# pig_led.net
KiCad netlist of a schematic drawn in EAGLE
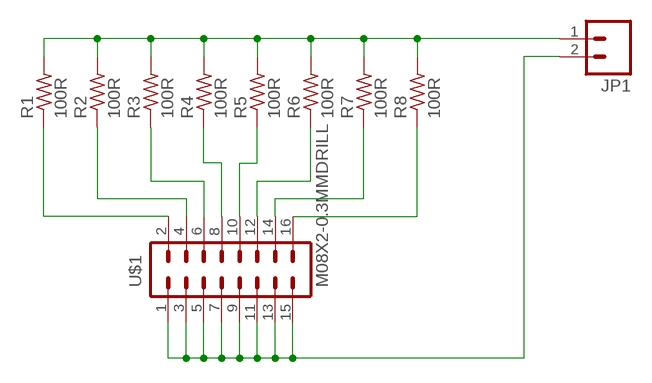
[diagram p0: schematic, sheet 1]

(export (version "E")
  (design (tool "Eeschema 10.0.6"))
  (components
    (comp (ref "JP1")
      (value "M023.5MM")
      (footprint "eagle-import:SCREWTERMINAL-3.5MM-2")
      (libsource (lib "eagle-import") (part "M023.5MM"))
    )
    (comp (ref "R1")
      (value "100R")
      (footprint "eagle-import:0207_10")
      (libsource (lib "eagle-import") (part "RESISTOR0207/10"))
    )
    (comp (ref "R2")
      (value "100R")
      (footprint "eagle-import:0207_10")
      (libsource (lib "eagle-import") (part "RESISTOR0207/10"))
    )
    (comp (ref "R3")
      (value "100R")
      (footprint "eagle-import:0207_10")
      (libsource (lib "eagle-import") (part "RESISTOR0207/10"))
    )
    (comp (ref "R4")
      (value "100R")
      (footprint "eagle-import:0207_10")
      (libsource (lib "eagle-import") (part "RESISTOR0207/10"))
    )
    (comp (ref "R5")
      (value "100R")
      (footprint "eagle-import:0207_10")
      (libsource (lib "eagle-import") (part "RESISTOR0207/10"))
    )
    (comp (ref "R6")
      (value "100R")
      (footprint "eagle-import:0207_10")
      (libsource (lib "eagle-import") (part "RESISTOR0207/10"))
    )
    (comp (ref "R7")
      (value "100R")
      (footprint "eagle-import:0207_10")
      (libsource (lib "eagle-import") (part "RESISTOR0207/10"))
    )
    (comp (ref "R8")
      (value "100R")
      (footprint "eagle-import:0207_10")
      (libsource (lib "eagle-import") (part "RESISTOR0207/10"))
    )
    (comp (ref "U$1")
      (value "M08X2-0.3MMDRILL")
      (footprint "eagle-import:2X8")
      (libsource (lib "eagle-import") (part "M08X2-0.3MMDRILL"))
    )
  )
  (nets
    (net (code "1") (name "Net-(JP1-Pad1)") (class "Default")
      (node (ref "JP1") (pin "1") (pinfunction "1_1") (pintype "passive"))
      (node (ref "R1") (pin "2") (pinfunction "2_2") (pintype "passive"))
      (node (ref "R2") (pin "2") (pinfunction "2_2") (pintype "passive"))
      (node (ref "R3") (pin "2") (pinfunction "2_2") (pintype "passive"))
      (node (ref "R4") (pin "2") (pinfunction "2_2") (pintype "passive"))
      (node (ref "R5") (pin "2") (pinfunction "2_2") (pintype "passive"))
      (node (ref "R6") (pin "2") (pinfunction "2_2") (pintype "passive"))
      (node (ref "R7") (pin "2") (pinfunction "2_2") (pintype "passive"))
      (node (ref "R8") (pin "2") (pinfunction "2_2") (pintype "passive"))
    )
    (net (code "2") (name "Net-(JP1-Pad2)") (class "Default")
      (node (ref "JP1") (pin "2") (pinfunction "2_2") (pintype "passive"))
      (node (ref "U$1") (pin "1") (pinfunction "1_1") (pintype "passive"))
      (node (ref "U$1") (pin "11") (pinfunction "11_11") (pintype "passive"))
      (node (ref "U$1") (pin "13") (pinfunction "13_13") (pintype "passive"))
      (node (ref "U$1") (pin "15") (pinfunction "15_15") (pintype "passive"))
      (node (ref "U$1") (pin "3") (pinfunction "3_3") (pintype "passive"))
      (node (ref "U$1") (pin "5") (pinfunction "5_5") (pintype "passive"))
      (node (ref "U$1") (pin "7") (pinfunction "7_7") (pintype "passive"))
      (node (ref "U$1") (pin "9") (pinfunction "9_9") (pintype "passive"))
    )
    (net (code "3") (name "Net-(R1-Pad1)") (class "Default")
      (node (ref "R1") (pin "1") (pinfunction "1_1") (pintype "passive"))
      (node (ref "U$1") (pin "2") (pinfunction "2_2") (pintype "passive"))
    )
    (net (code "4") (name "Net-(R2-Pad1)") (class "Default")
      (node (ref "R2") (pin "1") (pinfunction "1_1") (pintype "passive"))
      (node (ref "U$1") (pin "4") (pinfunction "4_4") (pintype "passive"))
    )
    (net (code "5") (name "Net-(R3-Pad1)") (class "Default")
      (node (ref "R3") (pin "1") (pinfunction "1_1") (pintype "passive"))
      (node (ref "U$1") (pin "6") (pinfunction "6_6") (pintype "passive"))
    )
    (net (code "6") (name "Net-(R4-Pad1)") (class "Default")
      (node (ref "R4") (pin "1") (pinfunction "1_1") (pintype "passive"))
      (node (ref "U$1") (pin "8") (pinfunction "8_8") (pintype "passive"))
    )
    (net (code "7") (name "Net-(R5-Pad1)") (class "Default")
      (node (ref "R5") (pin "1") (pinfunction "1_1") (pintype "passive"))
      (node (ref "U$1") (pin "10") (pinfunction "10_10") (pintype "passive"))
    )
    (net (code "8") (name "Net-(R6-Pad1)") (class "Default")
      (node (ref "R6") (pin "1") (pinfunction "1_1") (pintype "passive"))
      (node (ref "U$1") (pin "12") (pinfunction "12_12") (pintype "passive"))
    )
    (net (code "9") (name "Net-(R7-Pad1)") (class "Default")
      (node (ref "R7") (pin "1") (pinfunction "1_1") (pintype "passive"))
      (node (ref "U$1") (pin "14") (pinfunction "14_14") (pintype "passive"))
    )
    (net (code "10") (name "Net-(R8-Pad1)") (class "Default")
      (node (ref "R8") (pin "1") (pinfunction "1_1") (pintype "passive"))
      (node (ref "U$1") (pin "16") (pinfunction "16_16") (pintype "passive"))
    )
  )
)
